# AI_Thinker.net
KiCad netlist of a schematic drawn in Altium Designer
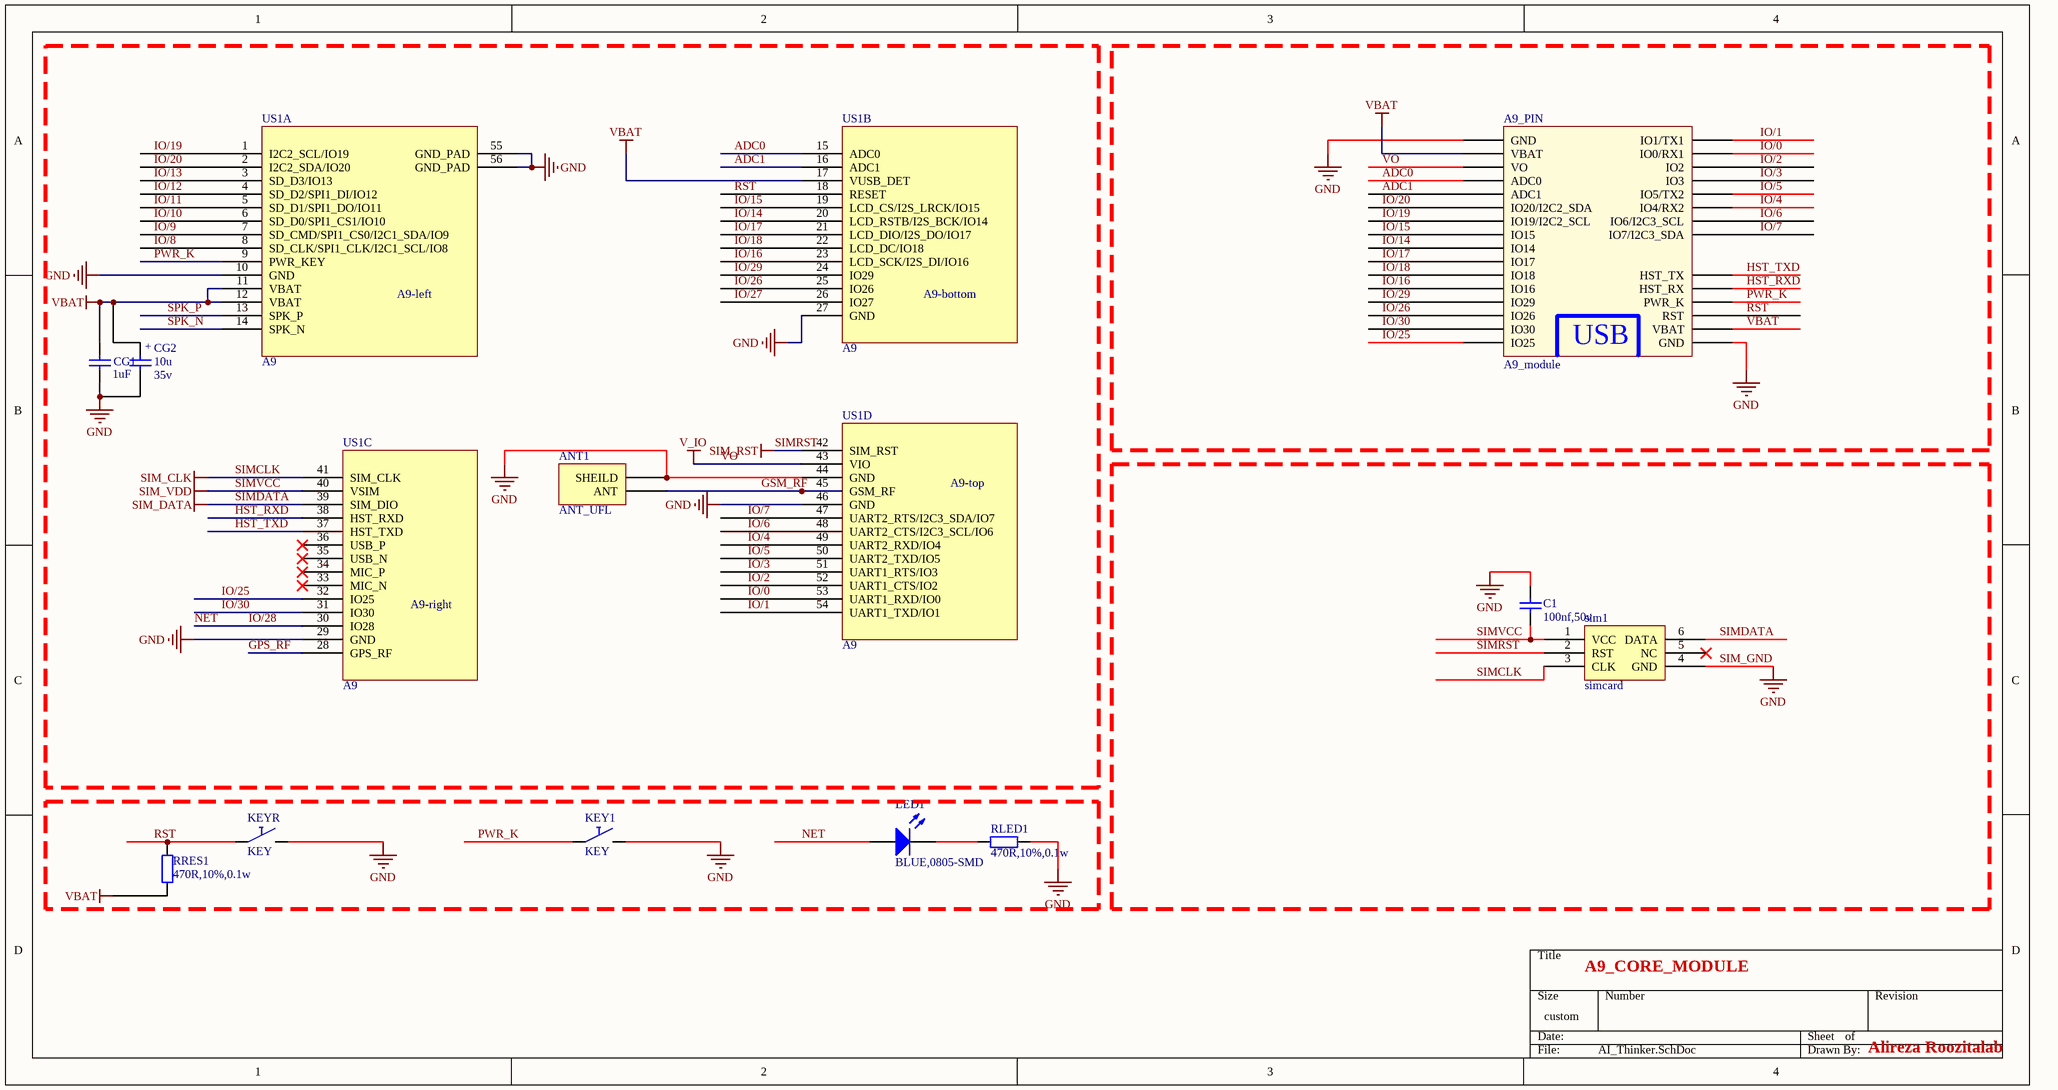
[diagram p0: AI_Thinker.SchDoc]

(export (version "E")
  (design (tool "Eeschema 10.0.6"))
  (components
    (comp (ref "A9_PIN")
      (value "A9_module")
      (footprint "A9_MODULE")
      (libsource (lib "armlib") (part "A9_module"))
    )
    (comp (ref "ANT1") (value "ANT_UFL") (footprint "UFL_CON") (libsource (lib "armlib") (part "ANT_UFL")))
    (comp (ref "C1")
      (value "100nf,50v")
      (footprint "0805.")
      (description "Capacitor")
      (fields (field (name "PUBLISHER") "Altium Limited"))
      (libsource (lib "STM32F407VG") (part "Cap"))
    )
    (comp (ref "CG1")
      (value "1uF")
      (footprint "CAP_SMD [1206]")
      (description "Capacitor")
      (libsource (lib "AllComponent") (part "Cap_smd [1206]"))
    )
    (comp (ref "CG2")
      (value "10u")
      (footprint "MY_SMC_D")
      (description "Polar capacitor")
      (fields (field (name "ASID PART NUMBER") "C-AS") (field (name "VOLTE") "35v"))
      (libsource (lib "TPS54331") (part "Cap Pol"))
    )
    (comp (ref "KEY1") (value "KEY") (footprint "SMD_KEY") (libsource (lib "armlib") (part "KEY")))
    (comp (ref "KEYR") (value "KEY") (footprint "SMD_KEY") (libsource (lib "armlib") (part "KEY")))
    (comp (ref "LED1")
      (value "BLUE,0805-SMD")
      (footprint "0805.")
      (description "Typical INFRARED GaAs LED")
      (fields (field (name "PUBLISHER") "Altium Limited"))
      (libsource (lib "MBIO-SCHPCB-MBFD-REV1") (part "LED0"))
    )
    (comp (ref "RLED1")
      (value "470R,10%,0.1w")
      (footprint "0805.")
      (description "Resistor")
      (fields (field (name "PUBLISHER") "Altium Limited"))
      (libsource (lib "") (part "Res2_1"))
    )
    (comp (ref "RRES1")
      (value "470R,10%,0.1w")
      (footprint "0805.")
      (description "Resistor")
      (fields (field (name "PUBLISHER") "Altium Limited"))
      (libsource (lib "MBIO-SCHPCB-MBFD-REV1") (part "Res2"))
    )
    (comp (ref "sim1") (value "simcard") (footprint "SIMCARD_M") (libsource (lib "armlib") (part "simcard")))
    (comp (ref "US1") (value "A9") (footprint "A9") (libsource (lib "A9") (part "A9")))
  )
  (nets
    (net (code "1") (name "/ADC0") (class "Default")
      (node (ref "A9_PIN") (pin "4") (pinfunction "ADC0_4") (pintype "passive"))
      (node (ref "US1") (pin "15") (pinfunction "ADC0_15") (pintype "passive"))
    )
    (net (code "2") (name "/ADC1") (class "Default")
      (node (ref "A9_PIN") (pin "5") (pinfunction "ADC1_5") (pintype "passive"))
      (node (ref "US1") (pin "16") (pinfunction "ADC1_16") (pintype "passive"))
    )
    (net (code "3") (name "/GPS_RF") (class "Default")
      (node (ref "US1") (pin "28") (pinfunction "GPS_RF_28") (pintype "passive"))
    )
    (net (code "4") (name "/GSM_RF") (class "Default")
      (node (ref "ANT1") (pin "2") (pinfunction "ANT_2") (pintype "passive"))
      (node (ref "US1") (pin "45") (pinfunction "GSM_RF_45") (pintype "passive"))
    )
    (net (code "5") (name "/HST_RXD") (class "Default")
      (node (ref "A9_PIN") (pin "21") (pinfunction "HST_RX_21") (pintype "passive"))
      (node (ref "US1") (pin "38") (pinfunction "HST_RXD_38") (pintype "passive"))
    )
    (net (code "6") (name "/HST_TXD") (class "Default")
      (node (ref "A9_PIN") (pin "22") (pinfunction "HST_TX_22") (pintype "passive"))
      (node (ref "US1") (pin "37") (pinfunction "HST_TXD_37") (pintype "passive"))
    )
    (net (code "7") (name "/IO{slash}0") (class "Default")
      (node (ref "A9_PIN") (pin "29") (pinfunction "IO0/RX1_29") (pintype "passive"))
      (node (ref "US1") (pin "53") (pinfunction "UART1_RXD/IO0_53") (pintype "passive"))
    )
    (net (code "8") (name "/IO{slash}1") (class "Default")
      (node (ref "A9_PIN") (pin "30") (pinfunction "IO1/TX1_30") (pintype "passive"))
      (node (ref "US1") (pin "54") (pinfunction "UART1_TXD/IO1_54") (pintype "passive"))
    )
    (net (code "9") (name "/IO{slash}2") (class "Default")
      (node (ref "A9_PIN") (pin "28") (pinfunction "IO2_28") (pintype "passive"))
      (node (ref "US1") (pin "52") (pinfunction "UART1_CTS/IO2_52") (pintype "passive"))
    )
    (net (code "10") (name "/IO{slash}3") (class "Default")
      (node (ref "A9_PIN") (pin "27") (pinfunction "IO3_27") (pintype "passive"))
      (node (ref "US1") (pin "51") (pinfunction "UART1_RTS/IO3_51") (pintype "passive"))
    )
    (net (code "11") (name "/IO{slash}4") (class "Default")
      (node (ref "A9_PIN") (pin "25") (pinfunction "IO4/RX2_25") (pintype "passive"))
      (node (ref "US1") (pin "49") (pinfunction "UART2_RXD/IO4_49") (pintype "passive"))
    )
    (net (code "12") (name "/IO{slash}5") (class "Default")
      (node (ref "A9_PIN") (pin "26") (pinfunction "IO5/TX2_26") (pintype "passive"))
      (node (ref "US1") (pin "50") (pinfunction "UART2_TXD/IO5_50") (pintype "passive"))
    )
    (net (code "13") (name "/IO{slash}6") (class "Default")
      (node (ref "A9_PIN") (pin "24") (pinfunction "IO6/I2C3_SCL_24") (pintype "passive"))
      (node (ref "US1") (pin "48") (pinfunction "UART2_CTS/I2C3_SCL/IO6_48") (pintype "passive"))
    )
    (net (code "14") (name "/IO{slash}7") (class "Default")
      (node (ref "A9_PIN") (pin "23") (pinfunction "IO7/I2C3_SDA_23") (pintype "passive"))
      (node (ref "US1") (pin "47") (pinfunction "UART2_RTS/I2C3_SDA/IO7_47") (pintype "passive"))
    )
    (net (code "15") (name "/IO{slash}8") (class "Default")
      (node (ref "US1") (pin "8") (pinfunction "SD_CLK/SPI1_CLK/I2C1_SCL/IO8_8") (pintype "passive"))
    )
    (net (code "16") (name "/IO{slash}9") (class "Default")
      (node (ref "US1") (pin "7") (pinfunction "SD_CMD/SPI1_CS0/I2C1_SDA/IO9_7") (pintype "passive"))
    )
    (net (code "17") (name "/IO{slash}10") (class "Default")
      (node (ref "US1") (pin "6") (pinfunction "SD_D0/SPI1_CS1/IO10_6") (pintype "passive"))
    )
    (net (code "18") (name "/IO{slash}11") (class "Default")
      (node (ref "US1") (pin "5") (pinfunction "SD_D1/SPI1_DO/IO11_5") (pintype "passive"))
    )
    (net (code "19") (name "/IO{slash}12") (class "Default")
      (node (ref "US1") (pin "4") (pinfunction "SD_D2/SPI1_DI/IO12_4") (pintype "passive"))
    )
    (net (code "20") (name "/IO{slash}13") (class "Default")
      (node (ref "US1") (pin "3") (pinfunction "SD_D3/IO13_3") (pintype "passive"))
    )
    (net (code "21") (name "/IO{slash}14") (class "Default")
      (node (ref "A9_PIN") (pin "9") (pinfunction "IO14_9") (pintype "passive"))
      (node (ref "US1") (pin "20") (pinfunction "LCD_RSTB/I2S_BCK/IO14_20") (pintype "passive"))
    )
    (net (code "22") (name "/IO{slash}15") (class "Default")
      (node (ref "A9_PIN") (pin "8") (pinfunction "IO15_8") (pintype "passive"))
      (node (ref "US1") (pin "19") (pinfunction "LCD_CS/I2S_LRCK/IO15_19") (pintype "passive"))
    )
    (net (code "23") (name "/IO{slash}16") (class "Default")
      (node (ref "A9_PIN") (pin "12") (pinfunction "IO16_12") (pintype "passive"))
      (node (ref "US1") (pin "23") (pinfunction "LCD_SCK/I2S_DI/IO16_23") (pintype "passive"))
    )
    (net (code "24") (name "/IO{slash}17") (class "Default")
      (node (ref "A9_PIN") (pin "10") (pinfunction "IO17_10") (pintype "passive"))
      (node (ref "US1") (pin "21") (pinfunction "LCD_DIO/I2S_DO/IO17_21") (pintype "passive"))
    )
    (net (code "25") (name "/IO{slash}18") (class "Default")
      (node (ref "A9_PIN") (pin "11") (pinfunction "IO18_11") (pintype "passive"))
      (node (ref "US1") (pin "22") (pinfunction "LCD_DC/IO18_22") (pintype "passive"))
    )
    (net (code "26") (name "/IO{slash}19") (class "Default")
      (node (ref "A9_PIN") (pin "7") (pinfunction "IO19/I2C2_SCL_7") (pintype "passive"))
      (node (ref "US1") (pin "1") (pinfunction "I2C2_SCL/IO19_1") (pintype "passive"))
    )
    (net (code "27") (name "/IO{slash}20") (class "Default")
      (node (ref "A9_PIN") (pin "6") (pinfunction "IO20/I2C2_SDA_6") (pintype "passive"))
      (node (ref "US1") (pin "2") (pinfunction "I2C2_SDA/IO20_2") (pintype "passive"))
    )
    (net (code "28") (name "/IO{slash}25") (class "Default")
      (node (ref "A9_PIN") (pin "16") (pinfunction "IO25_16") (pintype "passive"))
      (node (ref "US1") (pin "32") (pinfunction "IO25_32") (pintype "passive"))
    )
    (net (code "29") (name "/IO{slash}26") (class "Default")
      (node (ref "A9_PIN") (pin "14") (pinfunction "IO26_14") (pintype "passive"))
      (node (ref "US1") (pin "25") (pinfunction "IO26_25") (pintype "passive"))
    )
    (net (code "30") (name "/IO{slash}27") (class "Default")
      (node (ref "US1") (pin "26") (pinfunction "IO27_26") (pintype "passive"))
    )
    (net (code "31") (name "/IO{slash}28") (class "Default")
      (node (ref "LED1") (pin "2") (pinfunction "A_2") (pintype "passive"))
      (node (ref "US1") (pin "30") (pinfunction "IO28_30") (pintype "passive"))
    )
    (net (code "32") (name "/IO{slash}29") (class "Default")
      (node (ref "A9_PIN") (pin "13") (pinfunction "IO29_13") (pintype "passive"))
      (node (ref "US1") (pin "24") (pinfunction "IO29_24") (pintype "passive"))
    )
    (net (code "33") (name "/IO{slash}30") (class "Default")
      (node (ref "A9_PIN") (pin "15") (pinfunction "IO30_15") (pintype "passive"))
      (node (ref "US1") (pin "31") (pinfunction "IO30_31") (pintype "passive"))
    )
    (net (code "34") (name "/PWR_K") (class "Default")
      (node (ref "A9_PIN") (pin "20") (pinfunction "PWR_K_20") (pintype "passive"))
      (node (ref "KEY1") (pin "1") (pinfunction "1_1") (pintype "passive"))
      (node (ref "US1") (pin "9") (pinfunction "PWR_KEY_9") (pintype "passive"))
    )
    (net (code "35") (name "/RST") (class "Default")
      (node (ref "A9_PIN") (pin "19") (pinfunction "RST_19") (pintype "passive"))
      (node (ref "KEYR") (pin "1") (pinfunction "1_1") (pintype "passive"))
      (node (ref "RRES1") (pin "2") (pinfunction "2_2") (pintype "passive"))
      (node (ref "US1") (pin "18") (pinfunction "RESET_18") (pintype "passive"))
    )
    (net (code "36") (name "/SPK_N") (class "Default")
      (node (ref "US1") (pin "14") (pinfunction "SPK_N_14") (pintype "passive"))
    )
    (net (code "37") (name "/SPK_P") (class "Default")
      (node (ref "US1") (pin "13") (pinfunction "SPK_P_13") (pintype "passive"))
    )
    (net (code "38") (name "GND") (class "Default")
      (node (ref "A9_PIN") (pin "1") (pinfunction "GND_1") (pintype "passive"))
      (node (ref "A9_PIN") (pin "17") (pinfunction "GND_17") (pintype "passive"))
      (node (ref "ANT1") (pin "1") (pinfunction "SHEILD_1") (pintype "passive"))
      (node (ref "C1") (pin "2") (pinfunction "2_2") (pintype "passive"))
      (node (ref "CG1") (pin "1") (pinfunction "1_1") (pintype "passive"))
      (node (ref "CG2") (pin "-") (pinfunction "-_-") (pintype "passive"))
      (node (ref "KEY1") (pin "2") (pinfunction "2_2") (pintype "passive"))
      (node (ref "KEYR") (pin "2") (pinfunction "2_2") (pintype "passive"))
      (node (ref "RLED1") (pin "2") (pinfunction "2_2") (pintype "passive"))
      (node (ref "US1") (pin "10") (pinfunction "GND_10") (pintype "passive"))
      (node (ref "US1") (pin "27") (pinfunction "GND_27") (pintype "passive"))
      (node (ref "US1") (pin "29") (pinfunction "GND_29") (pintype "passive"))
      (node (ref "US1") (pin "44") (pinfunction "GND_44") (pintype "passive"))
      (node (ref "US1") (pin "46") (pinfunction "GND_46") (pintype "passive"))
      (node (ref "US1") (pin "55") (pinfunction "GND_PAD_55") (pintype "passive"))
      (node (ref "US1") (pin "56") (pinfunction "GND_PAD_56") (pintype "passive"))
      (node (ref "sim1") (pin "4") (pinfunction "GND_4") (pintype "passive"))
    )
    (net (code "39") (name "Net-(LED1-K)") (class "Default")
      (node (ref "LED1") (pin "1") (pinfunction "K_1") (pintype "passive"))
      (node (ref "RLED1") (pin "1") (pinfunction "1_1") (pintype "passive"))
    )
    (net (code "40") (name "SIM_CLK") (class "Default")
      (node (ref "US1") (pin "41") (pinfunction "SIM_CLK_41") (pintype "passive"))
      (node (ref "sim1") (pin "3") (pinfunction "CLK_3") (pintype "passive"))
    )
    (net (code "41") (name "SIM_DATA") (class "Default")
      (node (ref "US1") (pin "39") (pinfunction "SIM_DIO_39") (pintype "passive"))
      (node (ref "sim1") (pin "6") (pinfunction "DATA_6") (pintype "passive"))
    )
    (net (code "42") (name "SIM_RST") (class "Default")
      (node (ref "US1") (pin "42") (pinfunction "SIM_RST_42") (pintype "passive"))
      (node (ref "sim1") (pin "2") (pinfunction "RST_2") (pintype "passive"))
    )
    (net (code "43") (name "SIM_VDD") (class "Default")
      (node (ref "C1") (pin "1") (pinfunction "1_1") (pintype "passive"))
      (node (ref "US1") (pin "40") (pinfunction "VSIM_40") (pintype "passive"))
      (node (ref "sim1") (pin "1") (pinfunction "VCC_1") (pintype "passive"))
    )
    (net (code "44") (name "VBAT") (class "Default")
      (node (ref "A9_PIN") (pin "18") (pinfunction "VBAT_18") (pintype "passive"))
      (node (ref "A9_PIN") (pin "2") (pinfunction "VBAT_2") (pintype "passive"))
      (node (ref "CG1") (pin "2") (pinfunction "2_2") (pintype "passive"))
      (node (ref "CG2") (pin "+") (pinfunction "+_+") (pintype "passive"))
      (node (ref "RRES1") (pin "1") (pinfunction "1_1") (pintype "passive"))
      (node (ref "US1") (pin "11") (pinfunction "VBAT_11") (pintype "passive"))
      (node (ref "US1") (pin "12") (pinfunction "VBAT_12") (pintype "passive"))
      (node (ref "US1") (pin "17") (pinfunction "VUSB_DET_17") (pintype "passive"))
    )
    (net (code "45") (name "V_IO") (class "Default")
      (node (ref "A9_PIN") (pin "3") (pinfunction "VO_3") (pintype "passive"))
      (node (ref "US1") (pin "43") (pinfunction "VIO_43") (pintype "passive"))
    )
    (net (code "46") (name "unconnected-(US1C-MIC_N-Pad33)") (class "Default")
      (node (ref "US1") (pin "33") (pinfunction "MIC_N_33") (pintype "passive+no_connect"))
    )
    (net (code "47") (name "unconnected-(US1C-MIC_P-Pad34)") (class "Default")
      (node (ref "US1") (pin "34") (pinfunction "MIC_P_34") (pintype "passive+no_connect"))
    )
    (net (code "48") (name "unconnected-(US1C-USB_N-Pad35)") (class "Default")
      (node (ref "US1") (pin "35") (pinfunction "USB_N_35") (pintype "passive+no_connect"))
    )
    (net (code "49") (name "unconnected-(US1C-USB_P-Pad36)") (class "Default")
      (node (ref "US1") (pin "36") (pinfunction "USB_P_36") (pintype "passive+no_connect"))
    )
    (net (code "50") (name "unconnected-(sim1-NC-Pad5)") (class "Default")
      (node (ref "sim1") (pin "5") (pinfunction "NC_5") (pintype "passive+no_connect"))
    )
  )
)
